# Felfil_PCB_0_9.net
KiCad netlist of a schematic drawn in EAGLE
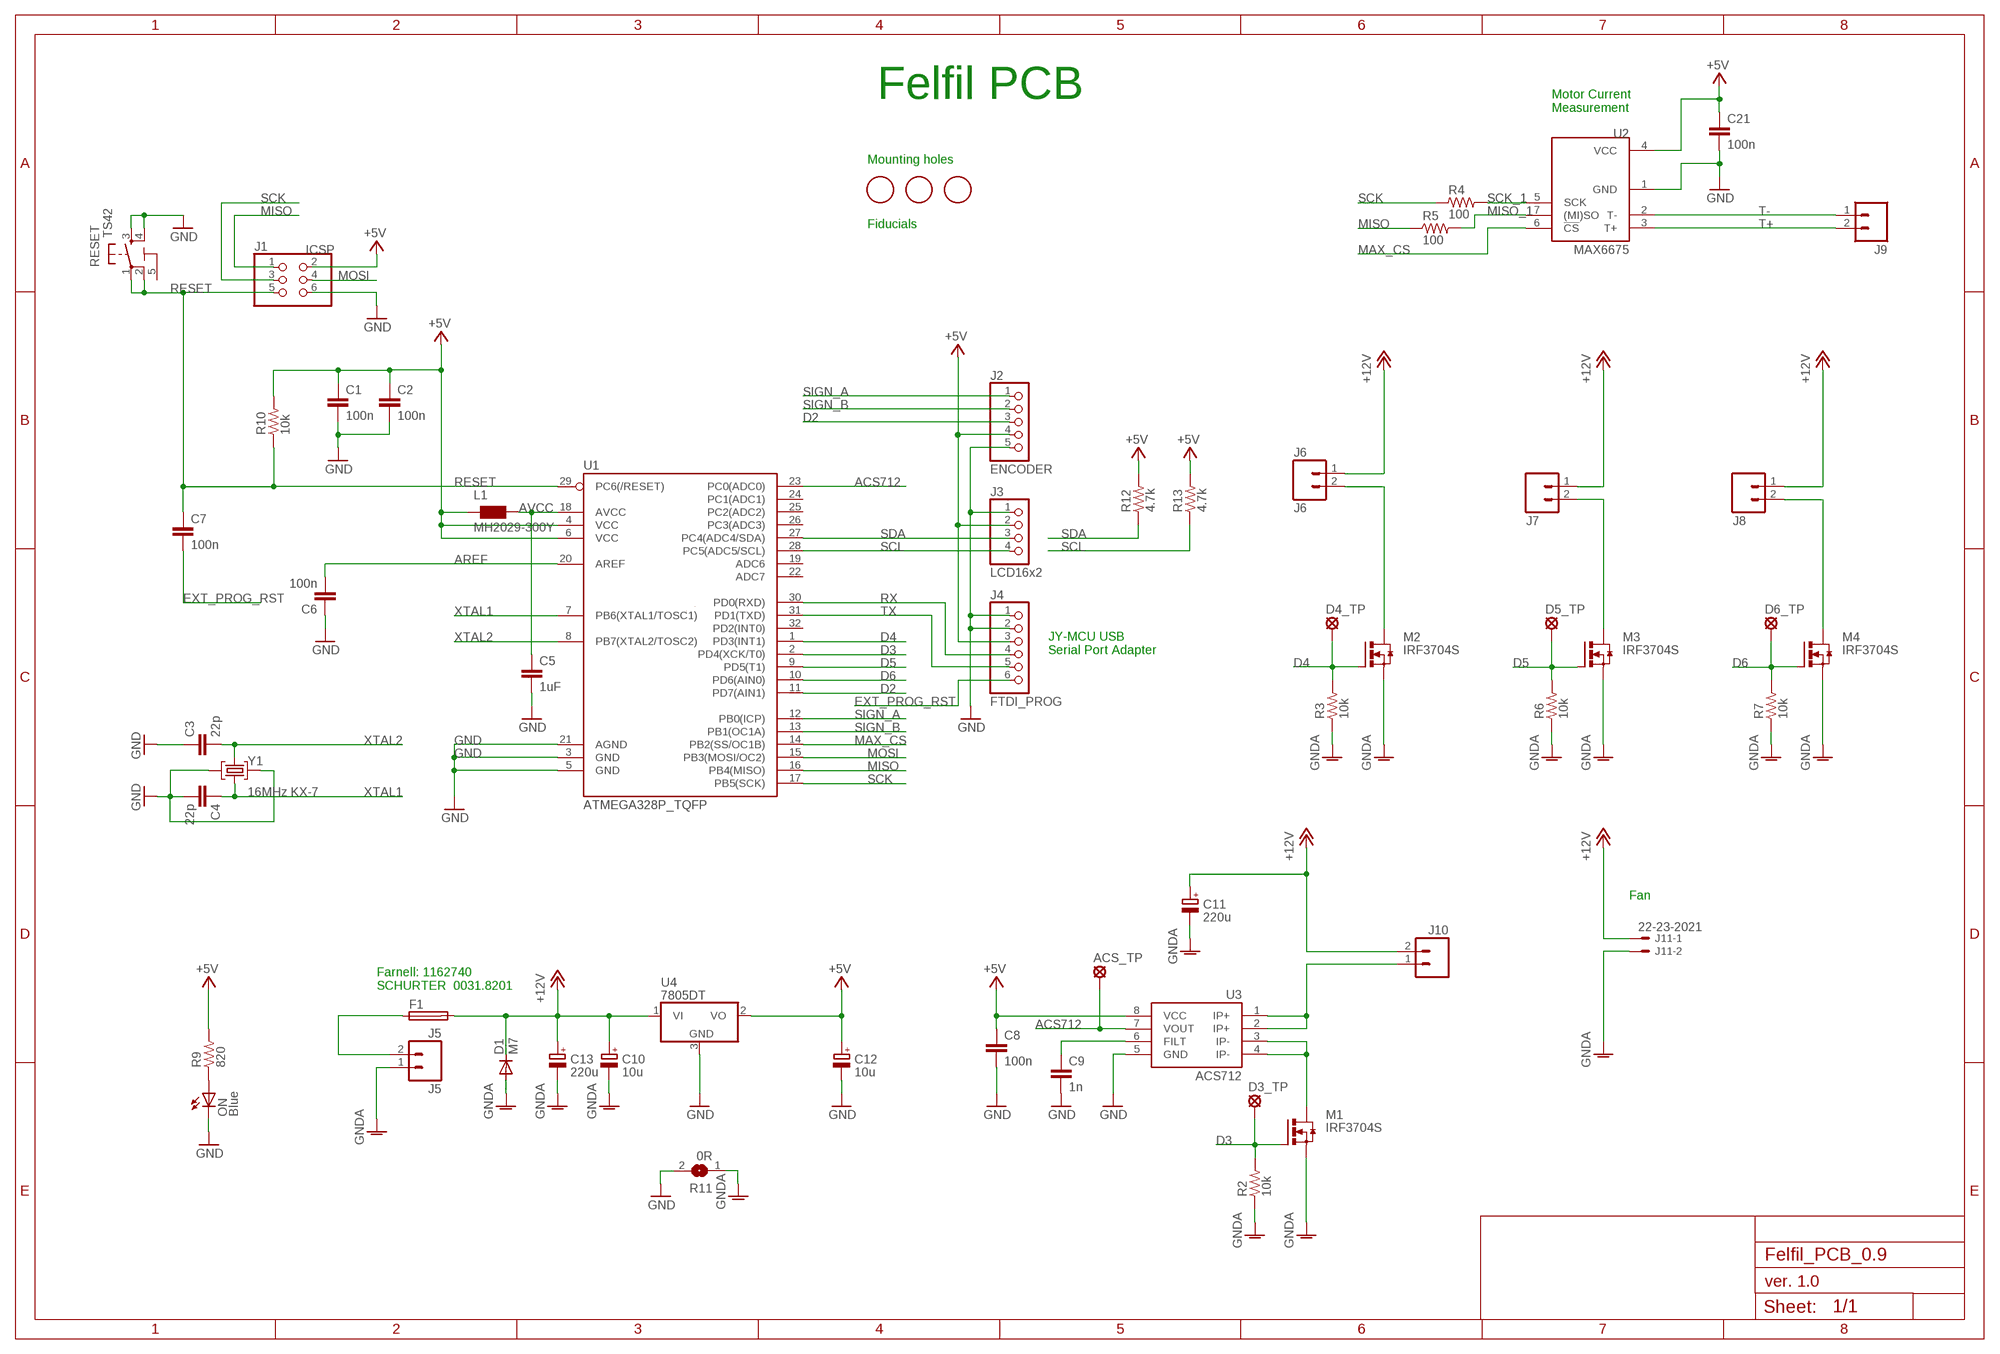
[diagram p0: schematic, sheet 1]

(export (version "E")
  (design (tool "Eeschema 10.0.6"))
  (components
    (comp (ref "ACS_TP")
      (value "LSP11")
      (footprint "eagle-import:LSP11")
      (libsource (lib "eagle-import") (part "LSP11"))
    )
    (comp (ref "C1")
      (value "100n")
      (footprint "eagle-import:C0603K")
      (libsource (lib "eagle-import") (part "C-EUC0603K"))
    )
    (comp (ref "C2")
      (value "100n")
      (footprint "eagle-import:C0603K")
      (libsource (lib "eagle-import") (part "C-EUC0603K"))
    )
    (comp (ref "C3")
      (value "22p")
      (footprint "eagle-import:C0603K")
      (libsource (lib "eagle-import") (part "C-EUC0603K"))
    )
    (comp (ref "C4")
      (value "22p")
      (footprint "eagle-import:C0603K")
      (libsource (lib "eagle-import") (part "C-EUC0603K"))
    )
    (comp (ref "C5")
      (value "1uF")
      (footprint "eagle-import:C0603K")
      (libsource (lib "eagle-import") (part "C-EUC0603K"))
    )
    (comp (ref "C6")
      (value "100n")
      (footprint "eagle-import:C0603K")
      (libsource (lib "eagle-import") (part "C-EUC0603K"))
    )
    (comp (ref "C7")
      (value "100n")
      (footprint "eagle-import:C0603K")
      (libsource (lib "eagle-import") (part "C-EUC0603K"))
    )
    (comp (ref "C8")
      (value "100n")
      (footprint "eagle-import:C0603K")
      (libsource (lib "eagle-import") (part "C-EUC0603K"))
    )
    (comp (ref "C9")
      (value "1n")
      (footprint "eagle-import:C0603K")
      (libsource (lib "eagle-import") (part "C-EUC0603K"))
    )
    (comp (ref "C10")
      (value "10u")
      (footprint "eagle-import:SMC_B")
      (libsource (lib "eagle-import") (part "CPOL-EUSMCB"))
    )
    (comp (ref "C11")
      (value "220u")
      (footprint "eagle-import:PANASONIC_F")
      (libsource (lib "eagle-import") (part "CPOL-EUF"))
    )
    (comp (ref "C12")
      (value "10u")
      (footprint "eagle-import:SMC_B")
      (libsource (lib "eagle-import") (part "CPOL-EUSMCB"))
    )
    (comp (ref "C13")
      (value "220u")
      (footprint "eagle-import:PANASONIC_F")
      (libsource (lib "eagle-import") (part "CPOL-EUF"))
    )
    (comp (ref "C21")
      (value "100n")
      (footprint "eagle-import:C0603K")
      (libsource (lib "eagle-import") (part "C-EUC0603K"))
    )
    (comp (ref "D1")
      (value "M7")
      (footprint "eagle-import:SMB")
      (libsource (lib "eagle-import") (part "DIODE-SMB"))
    )
    (comp (ref "D3_TP")
      (value "LSP11")
      (footprint "eagle-import:LSP11")
      (libsource (lib "eagle-import") (part "LSP11"))
    )
    (comp (ref "D4_TP")
      (value "LSP11")
      (footprint "eagle-import:LSP11")
      (libsource (lib "eagle-import") (part "LSP11"))
    )
    (comp (ref "D5_TP")
      (value "LSP11")
      (footprint "eagle-import:LSP11")
      (libsource (lib "eagle-import") (part "LSP11"))
    )
    (comp (ref "D6_TP")
      (value "LSP11")
      (footprint "eagle-import:LSP11")
      (libsource (lib "eagle-import") (part "LSP11"))
    )
    (comp (ref "F1")
      (value "FUSEBLANK_5X20MM")
      (footprint "eagle-import:FUSE_HOLDER_5X20MM")
      (libsource (lib "eagle-import") (part "FUSEBLANK_5X20MM"))
    )
    (comp (ref "FID1")
      (value "FIDUCIALMOUNT")
      (footprint "eagle-import:FIDUCIA-MOUNT")
      (libsource (lib "eagle-import") (part "FIDUCIALMOUNT"))
    )
    (comp (ref "FID2")
      (value "FIDUCIALMOUNT")
      (footprint "eagle-import:FIDUCIA-MOUNT")
      (libsource (lib "eagle-import") (part "FIDUCIALMOUNT"))
    )
    (comp (ref "FID3")
      (value "FIDUCIALMOUNT")
      (footprint "eagle-import:FIDUCIA-MOUNT")
      (libsource (lib "eagle-import") (part "FIDUCIALMOUNT"))
    )
    (comp (ref "J1")
      (value "ICSP")
      (footprint "eagle-import:2X03")
      (libsource (lib "eagle-import") (part "PINHD-2X3"))
    )
    (comp (ref "J2")
      (value "ENCODER")
      (footprint "eagle-import:1X05")
      (libsource (lib "eagle-import") (part "PINHD-1X5_2.54"))
    )
    (comp (ref "J3")
      (value "LCD16x2")
      (footprint "eagle-import:1X04")
      (libsource (lib "eagle-import") (part "PINHD-1X4_2.54"))
    )
    (comp (ref "J4")
      (value "FTDI_PROG")
      (footprint "eagle-import:1X06")
      (libsource (lib "eagle-import") (part "PINHD-1X6_2.54"))
    )
    (comp (ref "J5")
      (value "J5")
      (footprint "eagle-import:SCREWTERMINAL-5MM-2")
      (libsource (lib "eagle-import") (part "M025MM"))
    )
    (comp (ref "J6")
      (value "J6")
      (footprint "eagle-import:SCREWTERMINAL-5MM-2")
      (libsource (lib "eagle-import") (part "M025MM"))
    )
    (comp (ref "J7")
      (value "M025MM")
      (footprint "eagle-import:SCREWTERMINAL-5MM-2")
      (libsource (lib "eagle-import") (part "M025MM"))
    )
    (comp (ref "J8")
      (value "M025MM")
      (footprint "eagle-import:SCREWTERMINAL-5MM-2")
      (libsource (lib "eagle-import") (part "M025MM"))
    )
    (comp (ref "J9")
      (value "M025MM")
      (footprint "eagle-import:SCREWTERMINAL-5MM-2")
      (libsource (lib "eagle-import") (part "M025MM"))
    )
    (comp (ref "J10")
      (value "M025MM")
      (footprint "eagle-import:SCREWTERMINAL-5MM-2")
      (libsource (lib "eagle-import") (part "M025MM"))
    )
    (comp (ref "J11")
      (value "22-23-2021")
      (footprint "eagle-import:22-23-2021")
      (fields (field (name "MF") "MOLEX"))
      (libsource (lib "eagle-import") (part "22-23-2021"))
    )
    (comp (ref "L1")
      (value "MH2029-300Y")
      (footprint "eagle-import:0805")
      (libsource (lib "eagle-import") (part "WE-CBF_0805"))
    )
    (comp (ref "M1")
      (value "IRF3704S")
      (footprint "eagle-import:D2PACK")
      (libsource (lib "eagle-import") (part "IRF3704S"))
    )
    (comp (ref "M2")
      (value "IRF3704S")
      (footprint "eagle-import:D2PACK")
      (libsource (lib "eagle-import") (part "IRF3704S"))
    )
    (comp (ref "M3")
      (value "IRF3704S")
      (footprint "eagle-import:D2PACK")
      (libsource (lib "eagle-import") (part "IRF3704S"))
    )
    (comp (ref "M4")
      (value "IRF3704S")
      (footprint "eagle-import:D2PACK")
      (libsource (lib "eagle-import") (part "IRF3704S"))
    )
    (comp (ref "ON")
      (value "Blue")
      (footprint "eagle-import:CHIPLED_0805")
      (libsource (lib "eagle-import") (part "LEDCHIPLED_0805"))
    )
    (comp (ref "R2")
      (value "10k")
      (footprint "eagle-import:R0603")
      (libsource (lib "eagle-import") (part "R_0603"))
    )
    (comp (ref "R3")
      (value "10k")
      (footprint "eagle-import:R0603")
      (libsource (lib "eagle-import") (part "R_0603"))
    )
    (comp (ref "R4")
      (value "100")
      (footprint "eagle-import:R0603")
      (libsource (lib "eagle-import") (part "R_0603"))
    )
    (comp (ref "R5")
      (value "100")
      (footprint "eagle-import:R0603")
      (libsource (lib "eagle-import") (part "R_0603"))
    )
    (comp (ref "R6")
      (value "10k")
      (footprint "eagle-import:R0603")
      (libsource (lib "eagle-import") (part "R_0603"))
    )
    (comp (ref "R7")
      (value "10k")
      (footprint "eagle-import:R0603")
      (libsource (lib "eagle-import") (part "R_0603"))
    )
    (comp (ref "R9")
      (value "820")
      (footprint "eagle-import:R0603")
      (libsource (lib "eagle-import") (part "R_0603"))
    )
    (comp (ref "R10")
      (value "10k")
      (footprint "eagle-import:R0603")
      (libsource (lib "eagle-import") (part "R_0603"))
    )
    (comp (ref "R11")
      (value "0R")
      (footprint "eagle-import:SJW")
      (libsource (lib "eagle-import") (part "SJW"))
    )
    (comp (ref "R12")
      (value "4.7k")
      (footprint "eagle-import:R0603")
      (libsource (lib "eagle-import") (part "R_0603"))
    )
    (comp (ref "R13")
      (value "4.7k")
      (footprint "eagle-import:R0603")
      (libsource (lib "eagle-import") (part "R_0603"))
    )
    (comp (ref "RESET")
      (value "TS42")
      (footprint "eagle-import:TS42")
      (libsource (lib "eagle-import") (part "TS42"))
    )
    (comp (ref "U1")
      (value "ATMEGA328P_TQFP")
      (footprint "eagle-import:TQFP32-08")
      (libsource (lib "eagle-import") (part "ATMEGA328P_TQFP"))
    )
    (comp (ref "U2")
      (value "MAX6675")
      (footprint "eagle-import:SOIC8")
      (libsource (lib "eagle-import") (part "MAX6675"))
    )
    (comp (ref "U3")
      (value "ACS712")
      (footprint "eagle-import:SO08")
      (libsource (lib "eagle-import") (part "ACS712"))
    )
    (comp (ref "U4")
      (value "7805DT")
      (footprint "eagle-import:TO252")
      (libsource (lib "eagle-import") (part "78DT05"))
    )
    (comp (ref "Y1")
      (value "16MHz KX-7")
      (footprint "eagle-import:CRYSTAL-3.2-2.5")
      (libsource (lib "eagle-import") (part "CRYSTAL-3.2-2.5"))
    )
  )
  (nets
    (net (code "1") (name "+5V") (class "Default")
      (node (ref "C1") (pin "1") (pinfunction "1_1") (pintype "passive"))
      (node (ref "C12") (pin "+") (pinfunction "+_+") (pintype "passive"))
      (node (ref "C2") (pin "1") (pinfunction "1_1") (pintype "passive"))
      (node (ref "C21") (pin "1") (pinfunction "1_1") (pintype "passive"))
      (node (ref "C8") (pin "1") (pinfunction "1_1") (pintype "passive"))
      (node (ref "J1") (pin "2") (pinfunction "2_2") (pintype "passive"))
      (node (ref "J2") (pin "4") (pinfunction "4_4") (pintype "passive"))
      (node (ref "J3") (pin "2") (pinfunction "2_2") (pintype "passive"))
      (node (ref "J4") (pin "3") (pinfunction "3_3") (pintype "passive"))
      (node (ref "L1") (pin "1") (pinfunction "1_1") (pintype "passive"))
      (node (ref "R10") (pin "2") (pinfunction "2_2") (pintype "passive"))
      (node (ref "R12") (pin "2") (pinfunction "2_2") (pintype "passive"))
      (node (ref "R13") (pin "2") (pinfunction "2_2") (pintype "passive"))
      (node (ref "R9") (pin "2") (pinfunction "2_2") (pintype "passive"))
      (node (ref "U1") (pin "4") (pinfunction "VCC_4") (pintype "bidirectional"))
      (node (ref "U1") (pin "6") (pinfunction "VCC_6") (pintype "bidirectional"))
      (node (ref "U2") (pin "4") (pinfunction "VCC_4") (pintype "bidirectional"))
      (node (ref "U3") (pin "8") (pinfunction "VCC_8") (pintype "bidirectional"))
      (node (ref "U4") (pin "2") (pinfunction "VO_2") (pintype "passive"))
    )
    (net (code "2") (name "+12V") (class "Default")
      (node (ref "C10") (pin "+") (pinfunction "+_+") (pintype "passive"))
      (node (ref "C11") (pin "+") (pinfunction "+_+") (pintype "passive"))
      (node (ref "C13") (pin "+") (pinfunction "+_+") (pintype "passive"))
      (node (ref "D1") (pin "C") (pinfunction "C_C") (pintype "passive"))
      (node (ref "F1") (pin "2") (pinfunction "2_2") (pintype "passive"))
      (node (ref "J10") (pin "2") (pinfunction "2_2") (pintype "passive"))
      (node (ref "J11") (pin "1") (pinfunction "S_1") (pintype "passive"))
      (node (ref "J6") (pin "1") (pinfunction "1_1") (pintype "passive"))
      (node (ref "J7") (pin "1") (pinfunction "1_1") (pintype "passive"))
      (node (ref "J8") (pin "1") (pinfunction "1_1") (pintype "passive"))
      (node (ref "U4") (pin "1") (pinfunction "VI_1") (pintype "input"))
    )
    (net (code "3") (name "/5-GND") (class "Default")
      (node (ref "RESET") (pin "5") (pinfunction "5-GND_5") (pintype "power_in"))
    )
    (net (code "4") (name "/ACS712") (class "Default")
      (node (ref "ACS_TP") (pin "MP") (pinfunction "MP_MP") (pintype "passive"))
      (node (ref "U1") (pin "23") (pinfunction "PC0(ADC0)_23") (pintype "bidirectional"))
      (node (ref "U3") (pin "7") (pinfunction "VOUT_7") (pintype "bidirectional"))
    )
    (net (code "5") (name "/AREF") (class "Default")
      (node (ref "C6") (pin "2") (pinfunction "2_2") (pintype "passive"))
      (node (ref "U1") (pin "20") (pinfunction "AREF_20") (pintype "bidirectional"))
    )
    (net (code "6") (name "/AVCC") (class "Default")
      (node (ref "C5") (pin "1") (pinfunction "1_1") (pintype "passive"))
      (node (ref "L1") (pin "2") (pinfunction "2_2") (pintype "passive"))
      (node (ref "U1") (pin "18") (pinfunction "AVCC_18") (pintype "bidirectional"))
    )
    (net (code "7") (name "/D2") (class "Default")
      (node (ref "J2") (pin "3") (pinfunction "3_3") (pintype "passive"))
      (node (ref "U1") (pin "11") (pinfunction "PD7(AIN1)_11") (pintype "bidirectional"))
    )
    (net (code "8") (name "/D3") (class "Default")
      (node (ref "D3_TP") (pin "MP") (pinfunction "MP_MP") (pintype "passive"))
      (node (ref "M1") (pin "1") (pinfunction "G_1") (pintype "passive"))
      (node (ref "R2") (pin "2") (pinfunction "2_2") (pintype "passive"))
      (node (ref "U1") (pin "2") (pinfunction "PD4(XCK/T0)_2") (pintype "bidirectional"))
    )
    (net (code "9") (name "/D4") (class "Default")
      (node (ref "D4_TP") (pin "MP") (pinfunction "MP_MP") (pintype "passive"))
      (node (ref "M2") (pin "1") (pinfunction "G_1") (pintype "passive"))
      (node (ref "R3") (pin "2") (pinfunction "2_2") (pintype "passive"))
      (node (ref "U1") (pin "1") (pinfunction "PD3(INT1)_1") (pintype "bidirectional"))
    )
    (net (code "10") (name "/D5") (class "Default")
      (node (ref "D5_TP") (pin "MP") (pinfunction "MP_MP") (pintype "passive"))
      (node (ref "M3") (pin "1") (pinfunction "G_1") (pintype "passive"))
      (node (ref "R6") (pin "2") (pinfunction "2_2") (pintype "passive"))
      (node (ref "U1") (pin "9") (pinfunction "PD5(T1)_9") (pintype "bidirectional"))
    )
    (net (code "11") (name "/D6") (class "Default")
      (node (ref "D6_TP") (pin "MP") (pinfunction "MP_MP") (pintype "passive"))
      (node (ref "M4") (pin "1") (pinfunction "G_1") (pintype "passive"))
      (node (ref "R7") (pin "2") (pinfunction "2_2") (pintype "passive"))
      (node (ref "U1") (pin "10") (pinfunction "PD6(AIN0)_10") (pintype "bidirectional"))
    )
    (net (code "12") (name "/EXT_PROG_RST") (class "Default")
      (node (ref "C7") (pin "2") (pinfunction "2_2") (pintype "passive"))
      (node (ref "J4") (pin "6") (pinfunction "6_6") (pintype "passive"))
    )
    (net (code "13") (name "/MAX_CS") (class "Default")
      (node (ref "U1") (pin "14") (pinfunction "PB2(SS/OC1B)_14") (pintype "bidirectional"))
      (node (ref "U2") (pin "6") (pinfunction "~{CS}_6") (pintype "bidirectional"))
    )
    (net (code "14") (name "/MISO") (class "Default")
      (node (ref "J1") (pin "1") (pinfunction "1_1") (pintype "passive"))
      (node (ref "R5") (pin "1") (pinfunction "1_1") (pintype "passive"))
      (node (ref "U1") (pin "16") (pinfunction "PB4(MISO)_16") (pintype "bidirectional"))
    )
    (net (code "15") (name "/MISO_1") (class "Default")
      (node (ref "R5") (pin "2") (pinfunction "2_2") (pintype "passive"))
      (node (ref "U2") (pin "7") (pinfunction "(MI)SO_7") (pintype "bidirectional"))
    )
    (net (code "16") (name "/MOSI") (class "Default")
      (node (ref "J1") (pin "4") (pinfunction "4_4") (pintype "passive"))
      (node (ref "U1") (pin "15") (pinfunction "PB3(MOSI/OC2)_15") (pintype "bidirectional"))
    )
    (net (code "17") (name "/RESET") (class "Default")
      (node (ref "C7") (pin "1") (pinfunction "1_1") (pintype "passive"))
      (node (ref "J1") (pin "5") (pinfunction "5_5") (pintype "passive"))
      (node (ref "R10") (pin "1") (pinfunction "1_1") (pintype "passive"))
      (node (ref "RESET") (pin "1") (pinfunction "1_1") (pintype "passive"))
      (node (ref "RESET") (pin "2") (pinfunction "2_2") (pintype "passive"))
      (node (ref "U1") (pin "29") (pinfunction "PC6(/RESET)_29") (pintype "bidirectional"))
    )
    (net (code "18") (name "/RX") (class "Default")
      (node (ref "J4") (pin "4") (pinfunction "4_4") (pintype "passive"))
      (node (ref "U1") (pin "30") (pinfunction "PD0(RXD)_30") (pintype "bidirectional"))
    )
    (net (code "19") (name "/SCK") (class "Default")
      (node (ref "J1") (pin "3") (pinfunction "3_3") (pintype "passive"))
      (node (ref "R4") (pin "1") (pinfunction "1_1") (pintype "passive"))
      (node (ref "U1") (pin "17") (pinfunction "PB5(SCK)_17") (pintype "bidirectional"))
    )
    (net (code "20") (name "/SCK_1") (class "Default")
      (node (ref "R4") (pin "2") (pinfunction "2_2") (pintype "passive"))
      (node (ref "U2") (pin "5") (pinfunction "SCK_5") (pintype "bidirectional"))
    )
    (net (code "21") (name "/SCL") (class "Default")
      (node (ref "J3") (pin "4") (pinfunction "4_4") (pintype "passive"))
      (node (ref "R13") (pin "1") (pinfunction "1_1") (pintype "passive"))
      (node (ref "U1") (pin "28") (pinfunction "PC5(ADC5/SCL)_28") (pintype "bidirectional"))
    )
    (net (code "22") (name "/SDA") (class "Default")
      (node (ref "J3") (pin "3") (pinfunction "3_3") (pintype "passive"))
      (node (ref "R12") (pin "1") (pinfunction "1_1") (pintype "passive"))
      (node (ref "U1") (pin "27") (pinfunction "PC4(ADC4/SDA)_27") (pintype "bidirectional"))
    )
    (net (code "23") (name "/SIGN_A") (class "Default")
      (node (ref "J2") (pin "1") (pinfunction "1_1") (pintype "passive"))
      (node (ref "U1") (pin "12") (pinfunction "PB0(ICP)_12") (pintype "bidirectional"))
    )
    (net (code "24") (name "/SIGN_B") (class "Default")
      (node (ref "J2") (pin "2") (pinfunction "2_2") (pintype "passive"))
      (node (ref "U1") (pin "13") (pinfunction "PB1(OC1A)_13") (pintype "bidirectional"))
    )
    (net (code "25") (name "/T+") (class "Default")
      (node (ref "J9") (pin "2") (pinfunction "2_2") (pintype "passive"))
      (node (ref "U2") (pin "3") (pinfunction "T+_3") (pintype "bidirectional"))
    )
    (net (code "26") (name "/T-") (class "Default")
      (node (ref "J9") (pin "1") (pinfunction "1_1") (pintype "passive"))
      (node (ref "U2") (pin "2") (pinfunction "T-_2") (pintype "bidirectional"))
    )
    (net (code "27") (name "/TX") (class "Default")
      (node (ref "J4") (pin "5") (pinfunction "5_5") (pintype "passive"))
      (node (ref "U1") (pin "31") (pinfunction "PD1(TXD)_31") (pintype "bidirectional"))
    )
    (net (code "28") (name "/XTAL1") (class "Default")
      (node (ref "C4") (pin "1") (pinfunction "1_1") (pintype "passive"))
      (node (ref "U1") (pin "7") (pinfunction "PB6(XTAL1/TOSC1)_7") (pintype "bidirectional"))
      (node (ref "Y1") (pin "1") (pinfunction "C1_1") (pintype "passive"))
    )
    (net (code "29") (name "/XTAL2") (class "Default")
      (node (ref "C3") (pin "2") (pinfunction "2_2") (pintype "passive"))
      (node (ref "U1") (pin "8") (pinfunction "PB7(XTAL2/TOSC2)_8") (pintype "bidirectional"))
      (node (ref "Y1") (pin "3") (pinfunction "C2_3") (pintype "passive"))
    )
    (net (code "30") (name "GND") (class "Default")
      (node (ref "C1") (pin "2") (pinfunction "2_2") (pintype "passive"))
      (node (ref "C12") (pin "-") (pinfunction "-_-") (pintype "passive"))
      (node (ref "C2") (pin "2") (pinfunction "2_2") (pintype "passive"))
      (node (ref "C21") (pin "2") (pinfunction "2_2") (pintype "passive"))
      (node (ref "C3") (pin "1") (pinfunction "1_1") (pintype "passive"))
      (node (ref "C4") (pin "2") (pinfunction "2_2") (pintype "passive"))
      (node (ref "C5") (pin "2") (pinfunction "2_2") (pintype "passive"))
      (node (ref "C6") (pin "1") (pinfunction "1_1") (pintype "passive"))
      (node (ref "C8") (pin "2") (pinfunction "2_2") (pintype "passive"))
      (node (ref "C9") (pin "2") (pinfunction "2_2") (pintype "passive"))
      (node (ref "J1") (pin "6") (pinfunction "6_6") (pintype "passive"))
      (node (ref "J2") (pin "5") (pinfunction "5_5") (pintype "passive"))
      (node (ref "J3") (pin "1") (pinfunction "1_1") (pintype "passive"))
      (node (ref "J4") (pin "1") (pinfunction "1_1") (pintype "passive"))
      (node (ref "J4") (pin "2") (pinfunction "2_2") (pintype "passive"))
      (node (ref "ON") (pin "C") (pinfunction "C_C") (pintype "passive"))
      (node (ref "R11") (pin "2") (pinfunction "2_2") (pintype "passive"))
      (node (ref "RESET") (pin "3") (pinfunction "3_3") (pintype "passive"))
      (node (ref "RESET") (pin "4") (pinfunction "4_4") (pintype "passive"))
      (node (ref "U1") (pin "21") (pinfunction "AGND_21") (pintype "bidirectional"))
      (node (ref "U1") (pin "3") (pinfunction "GND_3") (pintype "bidirectional"))
      (node (ref "U1") (pin "5") (pinfunction "GND_5") (pintype "bidirectional"))
      (node (ref "U2") (pin "1") (pinfunction "GND_1") (pintype "bidirectional"))
      (node (ref "U3") (pin "5") (pinfunction "GND_5") (pintype "bidirectional"))
      (node (ref "U4") (pin "3") (pinfunction "GND_3") (pintype "passive"))
      (node (ref "Y1") (pin "2") (pinfunction "GND_2") (pintype "passive"))
      (node (ref "Y1") (pin "4") (pinfunction "GND_4") (pintype "passive"))
    )
    (net (code "31") (name "GNDA") (class "Default")
      (node (ref "C10") (pin "-") (pinfunction "-_-") (pintype "passive"))
      (node (ref "C11") (pin "-") (pinfunction "-_-") (pintype "passive"))
      (node (ref "C13") (pin "-") (pinfunction "-_-") (pintype "passive"))
      (node (ref "D1") (pin "A") (pinfunction "A_A") (pintype "passive"))
      (node (ref "J11") (pin "2") (pinfunction "S_2") (pintype "passive"))
      (node (ref "J5") (pin "1") (pinfunction "1_1") (pintype "passive"))
      (node (ref "M1") (pin "3") (pinfunction "S_3") (pintype "passive"))
      (node (ref "M2") (pin "3") (pinfunction "S_3") (pintype "passive"))
      (node (ref "M3") (pin "3") (pinfunction "S_3") (pintype "passive"))
      (node (ref "M4") (pin "3") (pinfunction "S_3") (pintype "passive"))
      (node (ref "R11") (pin "1") (pinfunction "1_1") (pintype "passive"))
      (node (ref "R2") (pin "1") (pinfunction "1_1") (pintype "passive"))
      (node (ref "R3") (pin "1") (pinfunction "1_1") (pintype "passive"))
      (node (ref "R6") (pin "1") (pinfunction "1_1") (pintype "passive"))
      (node (ref "R7") (pin "1") (pinfunction "1_1") (pintype "passive"))
    )
    (net (code "32") (name "Net-(F1-Pad1)") (class "Default")
      (node (ref "F1") (pin "1") (pinfunction "1_1") (pintype "passive"))
      (node (ref "J5") (pin "2") (pinfunction "2_2") (pintype "passive"))
    )
    (net (code "33") (name "Net-(J10-Pad1)") (class "Default")
      (node (ref "J10") (pin "1") (pinfunction "1_1") (pintype "passive"))
      (node (ref "U3") (pin "1") (pinfunction "IP+_1") (pintype "bidirectional"))
      (node (ref "U3") (pin "2") (pinfunction "IP+_2") (pintype "bidirectional"))
    )
    (net (code "34") (name "Net-(M1-D)") (class "Default")
      (node (ref "M1") (pin "2") (pinfunction "D_2") (pintype "passive"))
      (node (ref "U3") (pin "3") (pinfunction "IP-_3") (pintype "bidirectional"))
      (node (ref "U3") (pin "4") (pinfunction "IP-_4") (pintype "bidirectional"))
    )
    (net (code "35") (name "Net-(M2-D)") (class "Default")
      (node (ref "J6") (pin "2") (pinfunction "2_2") (pintype "passive"))
      (node (ref "M2") (pin "2") (pinfunction "D_2") (pintype "passive"))
    )
    (net (code "36") (name "Net-(M3-D)") (class "Default")
      (node (ref "J7") (pin "2") (pinfunction "2_2") (pintype "passive"))
      (node (ref "M3") (pin "2") (pinfunction "D_2") (pintype "passive"))
    )
    (net (code "37") (name "Net-(M4-D)") (class "Default")
      (node (ref "J8") (pin "2") (pinfunction "2_2") (pintype "passive"))
      (node (ref "M4") (pin "2") (pinfunction "D_2") (pintype "passive"))
    )
    (net (code "38") (name "Net-(ON-PadA)") (class "Default")
      (node (ref "ON") (pin "A") (pinfunction "A_A") (pintype "passive"))
      (node (ref "R9") (pin "1") (pinfunction "1_1") (pintype "passive"))
    )
    (net (code "39") (name "Net-(U3-FILT)") (class "Default")
      (node (ref "C9") (pin "1") (pinfunction "1_1") (pintype "passive"))
      (node (ref "U3") (pin "6") (pinfunction "FILT_6") (pintype "bidirectional"))
    )
    (net (code "40") (name "unconnected-(U1-ADC6-Pad19)") (class "Default")
      (node (ref "U1") (pin "19") (pinfunction "ADC6_19") (pintype "bidirectional"))
    )
    (net (code "41") (name "unconnected-(U1-ADC7-Pad22)") (class "Default")
      (node (ref "U1") (pin "22") (pinfunction "ADC7_22") (pintype "bidirectional"))
    )
    (net (code "42") (name "unconnected-(U1-PC1(ADC1)-Pad24)") (class "Default")
      (node (ref "U1") (pin "24") (pinfunction "PC1(ADC1)_24") (pintype "bidirectional"))
    )
    (net (code "43") (name "unconnected-(U1-PC2(ADC2)-Pad25)") (class "Default")
      (node (ref "U1") (pin "25") (pinfunction "PC2(ADC2)_25") (pintype "bidirectional"))
    )
    (net (code "44") (name "unconnected-(U1-PC3(ADC3)-Pad26)") (class "Default")
      (node (ref "U1") (pin "26") (pinfunction "PC3(ADC3)_26") (pintype "bidirectional"))
    )
    (net (code "45") (name "unconnected-(U1-PD2(INT0)-Pad32)") (class "Default")
      (node (ref "U1") (pin "32") (pinfunction "PD2(INT0)_32") (pintype "bidirectional"))
    )
  )
)
